# Atium_Designer_Schematic.net
KiCad netlist of a schematic drawn in Altium Designer
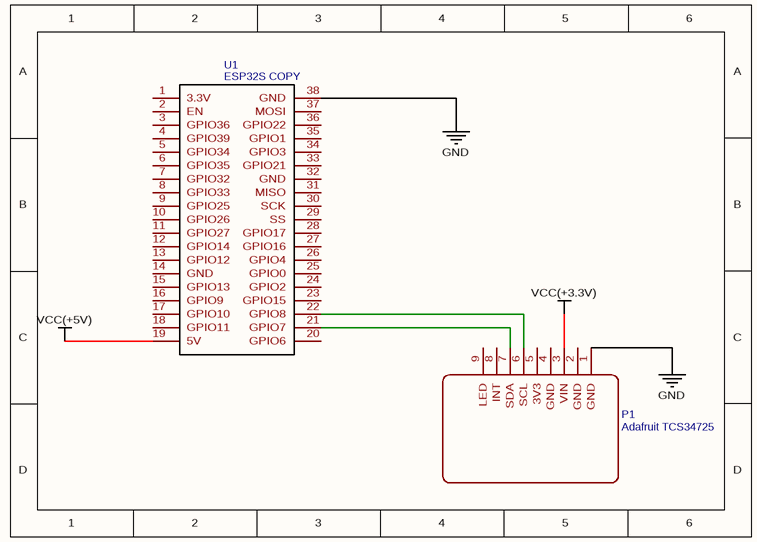
[diagram p0: Atium Designer Schematic.schdoc]

(export (version "E")
  (design (tool "Eeschema 10.0.6"))
  (components
    (comp (ref "P1")
      (value "Adafruit TCS34725")
      (libsource (lib "altium-import") (part "root_0_Adafruit TCS34725_"))
    )
    (comp (ref "U1")
      (value "ESP32S COPY")
      (fields (field (name "SUBPART_NO") "1") (field (name "CONTRIBUTOR") "DE018"))
      (libsource (lib "altium-import") (part "root_0_ESP32S COPY_"))
    )
  )
  (nets
    (net (code "1") (name "GND") (class "Default")
      (node (ref "P1") (pin "1") (pinfunction "GND_1") (pintype "passive"))
      (node (ref "U1") (pin "38") (pinfunction "GND_38") (pintype "passive"))
    )
    (net (code "2") (name "Net-(P1-SCL)") (class "Default")
      (node (ref "P1") (pin "6") (pinfunction "SCL_6") (pintype "passive"))
      (node (ref "U1") (pin "22") (pinfunction "GPIO8_22") (pintype "passive"))
    )
    (net (code "3") (name "Net-(P1-SDA)") (class "Default")
      (node (ref "P1") (pin "7") (pinfunction "SDA_7") (pintype "passive"))
      (node (ref "U1") (pin "21") (pinfunction "GPIO7_21") (pintype "passive"))
    )
    (net (code "4") (name "VCC(+3.3V)") (class "Default")
      (node (ref "P1") (pin "3") (pinfunction "VIN_3") (pintype "passive"))
    )
    (net (code "5") (name "VCC(+5V)") (class "Default")
      (node (ref "U1") (pin "19") (pinfunction "5V_19") (pintype "passive"))
    )
    (net (code "6") (name "unconnected-(P1-3V3-Pad5)") (class "Default")
      (node (ref "P1") (pin "5") (pinfunction "3V3_5") (pintype "passive"))
    )
    (net (code "7") (name "unconnected-(P1-GND-Pad2)") (class "Default")
      (node (ref "P1") (pin "2") (pinfunction "GND_2") (pintype "passive"))
    )
    (net (code "8") (name "unconnected-(P1-GND-Pad4)") (class "Default")
      (node (ref "P1") (pin "4") (pinfunction "GND_4") (pintype "passive"))
    )
    (net (code "9") (name "unconnected-(P1-INT-Pad8)") (class "Default")
      (node (ref "P1") (pin "8") (pinfunction "INT_8") (pintype "passive"))
    )
    (net (code "10") (name "unconnected-(P1-LED-Pad9)") (class "Default")
      (node (ref "P1") (pin "9") (pinfunction "LED_9") (pintype "passive"))
    )
    (net (code "11") (name "unconnected-(U1-3.3V-Pad1)") (class "Default")
      (node (ref "U1") (pin "1") (pinfunction "3.3V_1") (pintype "passive"))
    )
    (net (code "12") (name "unconnected-(U1-EN-Pad2)") (class "Default")
      (node (ref "U1") (pin "2") (pinfunction "EN_2") (pintype "passive"))
    )
    (net (code "13") (name "unconnected-(U1-GND-Pad14)") (class "Default")
      (node (ref "U1") (pin "14") (pinfunction "GND_14") (pintype "passive"))
    )
    (net (code "14") (name "unconnected-(U1-GND-Pad32)") (class "Default")
      (node (ref "U1") (pin "32") (pinfunction "GND_32") (pintype "passive"))
    )
    (net (code "15") (name "unconnected-(U1-GPIO0-Pad25)") (class "Default")
      (node (ref "U1") (pin "25") (pinfunction "GPIO0_25") (pintype "passive"))
    )
    (net (code "16") (name "unconnected-(U1-GPIO1-Pad35)") (class "Default")
      (node (ref "U1") (pin "35") (pinfunction "GPIO1_35") (pintype "passive"))
    )
    (net (code "17") (name "unconnected-(U1-GPIO2-Pad24)") (class "Default")
      (node (ref "U1") (pin "24") (pinfunction "GPIO2_24") (pintype "passive"))
    )
    (net (code "18") (name "unconnected-(U1-GPIO3-Pad34)") (class "Default")
      (node (ref "U1") (pin "34") (pinfunction "GPIO3_34") (pintype "passive"))
    )
    (net (code "19") (name "unconnected-(U1-GPIO4-Pad26)") (class "Default")
      (node (ref "U1") (pin "26") (pinfunction "GPIO4_26") (pintype "passive"))
    )
    (net (code "20") (name "unconnected-(U1-GPIO6-Pad20)") (class "Default")
      (node (ref "U1") (pin "20") (pinfunction "GPIO6_20") (pintype "passive"))
    )
    (net (code "21") (name "unconnected-(U1-GPIO9-Pad16)") (class "Default")
      (node (ref "U1") (pin "16") (pinfunction "GPIO9_16") (pintype "passive"))
    )
    (net (code "22") (name "unconnected-(U1-GPIO10-Pad17)") (class "Default")
      (node (ref "U1") (pin "17") (pinfunction "GPIO10_17") (pintype "passive"))
    )
    (net (code "23") (name "unconnected-(U1-GPIO11-Pad18)") (class "Default")
      (node (ref "U1") (pin "18") (pinfunction "GPIO11_18") (pintype "passive"))
    )
    (net (code "24") (name "unconnected-(U1-GPIO12-Pad13)") (class "Default")
      (node (ref "U1") (pin "13") (pinfunction "GPIO12_13") (pintype "passive"))
    )
    (net (code "25") (name "unconnected-(U1-GPIO13-Pad15)") (class "Default")
      (node (ref "U1") (pin "15") (pinfunction "GPIO13_15") (pintype "passive"))
    )
    (net (code "26") (name "unconnected-(U1-GPIO14-Pad12)") (class "Default")
      (node (ref "U1") (pin "12") (pinfunction "GPIO14_12") (pintype "passive"))
    )
    (net (code "27") (name "unconnected-(U1-GPIO15-Pad23)") (class "Default")
      (node (ref "U1") (pin "23") (pinfunction "GPIO15_23") (pintype "passive"))
    )
    (net (code "28") (name "unconnected-(U1-GPIO16-Pad27)") (class "Default")
      (node (ref "U1") (pin "27") (pinfunction "GPIO16_27") (pintype "passive"))
    )
    (net (code "29") (name "unconnected-(U1-GPIO17-Pad28)") (class "Default")
      (node (ref "U1") (pin "28") (pinfunction "GPIO17_28") (pintype "passive"))
    )
    (net (code "30") (name "unconnected-(U1-GPIO21-Pad33)") (class "Default")
      (node (ref "U1") (pin "33") (pinfunction "GPIO21_33") (pintype "passive"))
    )
    (net (code "31") (name "unconnected-(U1-GPIO22-Pad36)") (class "Default")
      (node (ref "U1") (pin "36") (pinfunction "GPIO22_36") (pintype "passive"))
    )
    (net (code "32") (name "unconnected-(U1-GPIO25-Pad9)") (class "Default")
      (node (ref "U1") (pin "9") (pinfunction "GPIO25_9") (pintype "passive"))
    )
    (net (code "33") (name "unconnected-(U1-GPIO26-Pad10)") (class "Default")
      (node (ref "U1") (pin "10") (pinfunction "GPIO26_10") (pintype "passive"))
    )
    (net (code "34") (name "unconnected-(U1-GPIO27-Pad11)") (class "Default")
      (node (ref "U1") (pin "11") (pinfunction "GPIO27_11") (pintype "passive"))
    )
    (net (code "35") (name "unconnected-(U1-GPIO32-Pad7)") (class "Default")
      (node (ref "U1") (pin "7") (pinfunction "GPIO32_7") (pintype "passive"))
    )
    (net (code "36") (name "unconnected-(U1-GPIO33-Pad8)") (class "Default")
      (node (ref "U1") (pin "8") (pinfunction "GPIO33_8") (pintype "passive"))
    )
    (net (code "37") (name "unconnected-(U1-GPIO34-Pad5)") (class "Default")
      (node (ref "U1") (pin "5") (pinfunction "GPIO34_5") (pintype "passive"))
    )
    (net (code "38") (name "unconnected-(U1-GPIO35-Pad6)") (class "Default")
      (node (ref "U1") (pin "6") (pinfunction "GPIO35_6") (pintype "passive"))
    )
    (net (code "39") (name "unconnected-(U1-GPIO36-Pad3)") (class "Default")
      (node (ref "U1") (pin "3") (pinfunction "GPIO36_3") (pintype "passive"))
    )
    (net (code "40") (name "unconnected-(U1-GPIO39-Pad4)") (class "Default")
      (node (ref "U1") (pin "4") (pinfunction "GPIO39_4") (pintype "passive"))
    )
    (net (code "41") (name "unconnected-(U1-MISO-Pad31)") (class "Default")
      (node (ref "U1") (pin "31") (pinfunction "MISO_31") (pintype "passive"))
    )
    (net (code "42") (name "unconnected-(U1-MOSI-Pad37)") (class "Default")
      (node (ref "U1") (pin "37") (pinfunction "MOSI_37") (pintype "passive"))
    )
    (net (code "43") (name "unconnected-(U1-SCK-Pad30)") (class "Default")
      (node (ref "U1") (pin "30") (pinfunction "SCK_30") (pintype "passive"))
    )
    (net (code "44") (name "unconnected-(U1-SS-Pad29)") (class "Default")
      (node (ref "U1") (pin "29") (pinfunction "SS_29") (pintype "passive"))
    )
  )
)
